# AeroQuad_v213.net
KiCad netlist of a schematic drawn in EAGLE
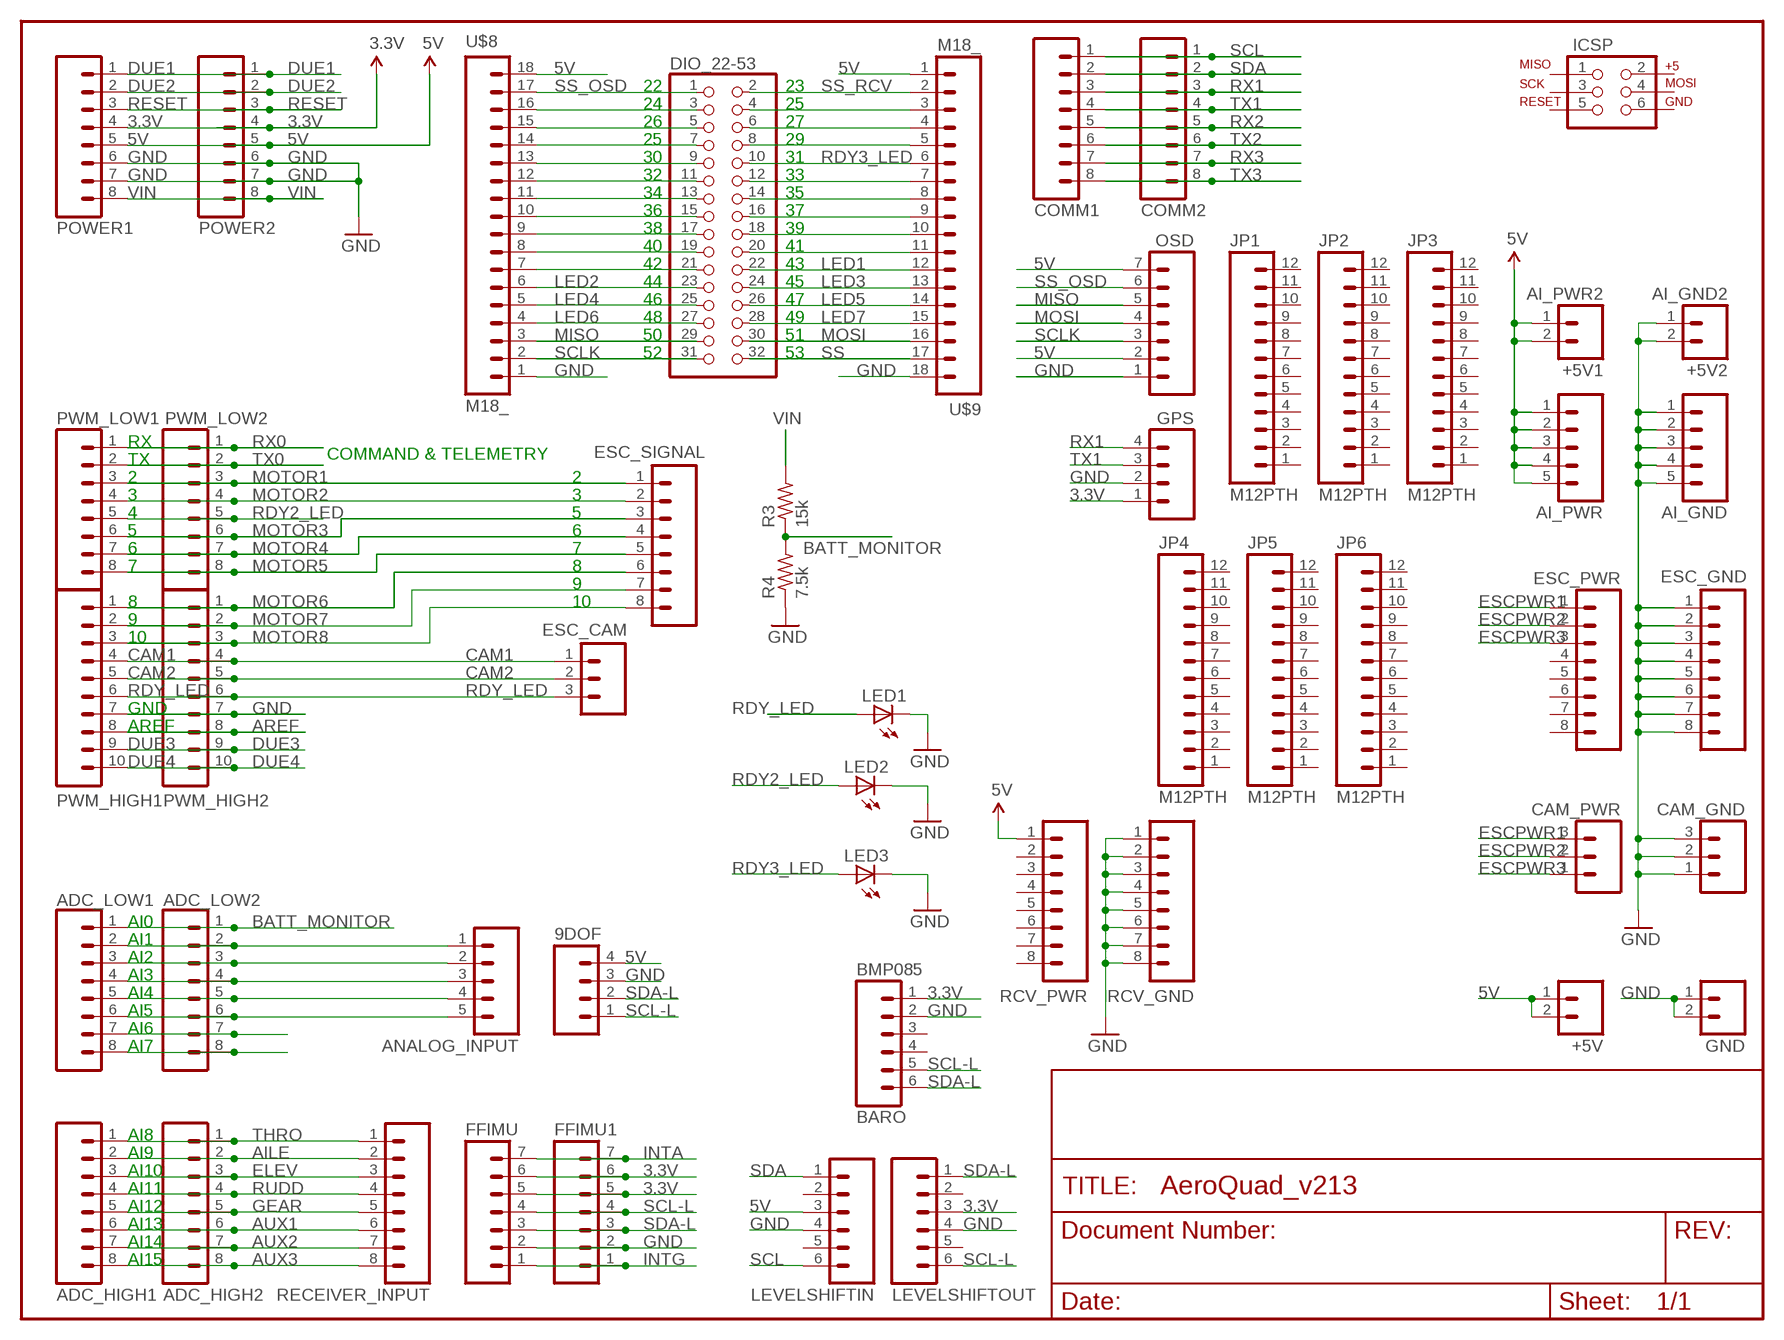
[diagram p0: schematic, sheet 1]

(export (version "E")
  (design (tool "Eeschema 10.0.6"))
  (components
    (comp (ref "+5V")
      (value "M02PTH")
      (footprint "eagle-import:1X02")
      (libsource (lib "eagle-import") (part "M02PTH"))
    )
    (comp (ref "+5V1")
      (value "AI_PWR2")
      (footprint "eagle-import:1X02")
      (libsource (lib "eagle-import") (part "M02PTH"))
    )
    (comp (ref "+5V2")
      (value "AI_GND2")
      (footprint "eagle-import:1X02")
      (libsource (lib "eagle-import") (part "M02PTH"))
    )
    (comp (ref "9DOF")
      (value "M04LOCK")
      (footprint "eagle-import:1X04_LOCK")
      (libsource (lib "eagle-import") (part "M04LOCK"))
    )
    (comp (ref "ADC_HIGH1")
      (value "M08LOCK")
      (footprint "eagle-import:1X08_LOCK")
      (libsource (lib "eagle-import") (part "M08LOCK"))
    )
    (comp (ref "ADC_HIGH2")
      (value "M08LOCK")
      (footprint "eagle-import:1X08_LOCK")
      (libsource (lib "eagle-import") (part "M08LOCK"))
    )
    (comp (ref "ADC_LOW1")
      (value "M08LOCK")
      (footprint "eagle-import:1X08_LOCK")
      (libsource (lib "eagle-import") (part "M08LOCK"))
    )
    (comp (ref "ADC_LOW2")
      (value "M08LOCK")
      (footprint "eagle-import:1X08_LOCK")
      (libsource (lib "eagle-import") (part "M08LOCK"))
    )
    (comp (ref "AI_GND")
      (value "M05LOCK")
      (footprint "eagle-import:1X05_LOCK")
      (libsource (lib "eagle-import") (part "M05LOCK"))
    )
    (comp (ref "AI_PWR")
      (value "M05LOCK")
      (footprint "eagle-import:1X05_LOCK")
      (libsource (lib "eagle-import") (part "M05LOCK"))
    )
    (comp (ref "ANALOG_INPUT")
      (value "M05LOCK")
      (footprint "eagle-import:1X05_LOCK")
      (libsource (lib "eagle-import") (part "M05LOCK"))
    )
    (comp (ref "BARO")
      (value "BMP085")
      (footprint "eagle-import:1X06_LOCK")
      (libsource (lib "eagle-import") (part "M06LOCK"))
    )
    (comp (ref "CAM_GND")
      (value "M03LOCK")
      (footprint "eagle-import:1X03_LOCK")
      (libsource (lib "eagle-import") (part "M03LOCK"))
    )
    (comp (ref "CAM_PWR")
      (value "M03LOCK")
      (footprint "eagle-import:1X03_LOCK")
      (libsource (lib "eagle-import") (part "M03LOCK"))
    )
    (comp (ref "COMM1")
      (value "M08LOCK")
      (footprint "eagle-import:1X08_LOCK")
      (libsource (lib "eagle-import") (part "M08LOCK"))
    )
    (comp (ref "COMM2")
      (value "M08LOCK")
      (footprint "eagle-import:1X08_LOCK")
      (libsource (lib "eagle-import") (part "M08LOCK"))
    )
    (comp (ref "DIO_22-53")
      (value "PINHD-2X16")
      (footprint "eagle-import:2X16")
      (libsource (lib "eagle-import") (part "PINHD-2X16"))
    )
    (comp (ref "ESC_CAM")
      (value "M03LOCK")
      (footprint "eagle-import:1X03_LOCK")
      (libsource (lib "eagle-import") (part "M03LOCK"))
    )
    (comp (ref "ESC_GND")
      (value "M10LOCK")
      (footprint "eagle-import:1X08_LOCK")
      (libsource (lib "eagle-import") (part "M08LOCK"))
    )
    (comp (ref "ESC_PWR")
      (value "M10LOCK")
      (footprint "eagle-import:1X08_LOCK")
      (libsource (lib "eagle-import") (part "M08LOCK"))
    )
    (comp (ref "ESC_SIGNAL")
      (value "M10LOCK")
      (footprint "eagle-import:1X08_LOCK")
      (libsource (lib "eagle-import") (part "M08LOCK"))
    )
    (comp (ref "FFIMU")
      (value "M07LOCK")
      (footprint "eagle-import:1X07_LOCK")
      (libsource (lib "eagle-import") (part "M07LOCK"))
    )
    (comp (ref "FFIMU1")
      (value "M07LOCK")
      (footprint "eagle-import:1X07_LOCK")
      (libsource (lib "eagle-import") (part "M07LOCK"))
    )
    (comp (ref "GND")
      (value "M02PTH")
      (footprint "eagle-import:1X02")
      (libsource (lib "eagle-import") (part "M02PTH"))
    )
    (comp (ref "GPS")
      (value "M04LOCK")
      (footprint "eagle-import:1X04_LOCK")
      (libsource (lib "eagle-import") (part "M04LOCK"))
    )
    (comp (ref "ICSP")
      (value "AVR_SPI_PRG_6NS")
      (footprint "eagle-import:2X3-NS")
      (libsource (lib "eagle-import") (part "AVR_SPI_PRG_6NS"))
    )
    (comp (ref "JP1")
      (value "M12PTH")
      (footprint "eagle-import:1X12")
      (libsource (lib "eagle-import") (part "M12PTH"))
    )
    (comp (ref "JP2")
      (value "M12PTH")
      (footprint "eagle-import:1X12")
      (libsource (lib "eagle-import") (part "M12PTH"))
    )
    (comp (ref "JP3")
      (value "M12PTH")
      (footprint "eagle-import:1X12")
      (libsource (lib "eagle-import") (part "M12PTH"))
    )
    (comp (ref "JP4")
      (value "M12PTH")
      (footprint "eagle-import:1X12")
      (libsource (lib "eagle-import") (part "M12PTH"))
    )
    (comp (ref "JP5")
      (value "M12PTH")
      (footprint "eagle-import:1X12")
      (libsource (lib "eagle-import") (part "M12PTH"))
    )
    (comp (ref "JP6")
      (value "M12PTH")
      (footprint "eagle-import:1X12")
      (libsource (lib "eagle-import") (part "M12PTH"))
    )
    (comp (ref "LED1")
      (value "LED5MM")
      (footprint "eagle-import:LED5MM")
      (libsource (lib "eagle-import") (part "LED5MM"))
    )
    (comp (ref "LED2")
      (value "LED5MM")
      (footprint "eagle-import:LED5MM")
      (libsource (lib "eagle-import") (part "LED5MM"))
    )
    (comp (ref "LED3")
      (value "LED5MM")
      (footprint "eagle-import:LED5MM")
      (libsource (lib "eagle-import") (part "LED5MM"))
    )
    (comp (ref "LEVELSHIFTIN")
      (value "M06LOCK")
      (footprint "eagle-import:1X06_LOCK")
      (libsource (lib "eagle-import") (part "M06LOCK"))
    )
    (comp (ref "LEVELSHIFTOUT")
      (value "M06LOCK")
      (footprint "eagle-import:1X06_LOCK")
      (libsource (lib "eagle-import") (part "M06LOCK"))
    )
    (comp (ref "OSD")
      (value "M07LOCK")
      (footprint "eagle-import:1X07_LOCK")
      (libsource (lib "eagle-import") (part "M07LOCK"))
    )
    (comp (ref "POWER1")
      (value "M08LOCK")
      (footprint "eagle-import:1X08_LOCK")
      (libsource (lib "eagle-import") (part "M08LOCK"))
    )
    (comp (ref "POWER2")
      (value "M08LOCK")
      (footprint "eagle-import:1X08_LOCK")
      (libsource (lib "eagle-import") (part "M08LOCK"))
    )
    (comp (ref "PWM_HIGH1")
      (value "M10LOCK")
      (footprint "eagle-import:1X10_LOCK")
      (libsource (lib "eagle-import") (part "M10LOCK"))
    )
    (comp (ref "PWM_HIGH2")
      (value "M10LOCK")
      (footprint "eagle-import:1X10_LOCK")
      (libsource (lib "eagle-import") (part "M10LOCK"))
    )
    (comp (ref "PWM_LOW1")
      (value "M08LOCK")
      (footprint "eagle-import:1X08_LOCK")
      (libsource (lib "eagle-import") (part "M08LOCK"))
    )
    (comp (ref "PWM_LOW2")
      (value "M08LOCK")
      (footprint "eagle-import:1X08_LOCK")
      (libsource (lib "eagle-import") (part "M08LOCK"))
    )
    (comp (ref "R3")
      (value "15k")
      (footprint "eagle-import:0204_5")
      (libsource (lib "eagle-import") (part "R-US_0204/5"))
    )
    (comp (ref "R4")
      (value "7.5k")
      (footprint "eagle-import:0204_5")
      (libsource (lib "eagle-import") (part "R-US_0204/5"))
    )
    (comp (ref "RCV_GND")
      (value "M10LOCK")
      (footprint "eagle-import:1X08_LOCK")
      (libsource (lib "eagle-import") (part "M08LOCK"))
    )
    (comp (ref "RCV_PWR")
      (value "M10LOCK")
      (footprint "eagle-import:1X08_LOCK")
      (libsource (lib "eagle-import") (part "M08LOCK"))
    )
    (comp (ref "RECEIVER_INPUT")
      (value "M08LOCK")
      (footprint "eagle-import:1X08_LOCK")
      (libsource (lib "eagle-import") (part "M08LOCK"))
    )
    (comp (ref "U$8")
      (value "M18_")
      (footprint "eagle-import:1X18")
      (libsource (lib "eagle-import") (part "M18_"))
    )
    (comp (ref "U$9")
      (value "M18_")
      (footprint "eagle-import:1X18")
      (libsource (lib "eagle-import") (part "M18_"))
    )
  )
  (nets
    (net (code "1") (name "/AILE") (class "Default")
      (node (ref "ADC_HIGH1") (pin "2") (pinfunction "2_2") (pintype "passive"))
      (node (ref "ADC_HIGH2") (pin "2") (pinfunction "2_2") (pintype "passive"))
      (node (ref "RECEIVER_INPUT") (pin "2") (pinfunction "2_2") (pintype "passive"))
    )
    (net (code "2") (name "/AREF") (class "Default")
      (node (ref "PWM_HIGH1") (pin "8") (pinfunction "8_8") (pintype "passive"))
      (node (ref "PWM_HIGH2") (pin "8") (pinfunction "8_8") (pintype "passive"))
    )
    (net (code "3") (name "/AUX1") (class "Default")
      (node (ref "ADC_HIGH1") (pin "6") (pinfunction "6_6") (pintype "passive"))
      (node (ref "ADC_HIGH2") (pin "6") (pinfunction "6_6") (pintype "passive"))
      (node (ref "RECEIVER_INPUT") (pin "6") (pinfunction "6_6") (pintype "passive"))
    )
    (net (code "4") (name "/AUX2") (class "Default")
      (node (ref "ADC_HIGH1") (pin "7") (pinfunction "7_7") (pintype "passive"))
      (node (ref "ADC_HIGH2") (pin "7") (pinfunction "7_7") (pintype "passive"))
      (node (ref "RECEIVER_INPUT") (pin "7") (pinfunction "7_7") (pintype "passive"))
    )
    (net (code "5") (name "/AUX3") (class "Default")
      (node (ref "ADC_HIGH1") (pin "8") (pinfunction "8_8") (pintype "passive"))
      (node (ref "ADC_HIGH2") (pin "8") (pinfunction "8_8") (pintype "passive"))
      (node (ref "RECEIVER_INPUT") (pin "8") (pinfunction "8_8") (pintype "passive"))
    )
    (net (code "6") (name "/BATT_MONITOR") (class "Default")
      (node (ref "ADC_LOW1") (pin "1") (pinfunction "1_1") (pintype "passive"))
      (node (ref "ADC_LOW2") (pin "1") (pinfunction "1_1") (pintype "passive"))
      (node (ref "R3") (pin "1") (pinfunction "1_1") (pintype "passive"))
      (node (ref "R4") (pin "2") (pinfunction "2_2") (pintype "passive"))
    )
    (net (code "7") (name "/CAM1") (class "Default")
      (node (ref "ESC_CAM") (pin "1") (pinfunction "1_1") (pintype "passive"))
      (node (ref "PWM_HIGH1") (pin "4") (pinfunction "4_4") (pintype "passive"))
      (node (ref "PWM_HIGH2") (pin "4") (pinfunction "4_4") (pintype "passive"))
    )
    (net (code "8") (name "/CAM2") (class "Default")
      (node (ref "ESC_CAM") (pin "2") (pinfunction "2_2") (pintype "passive"))
      (node (ref "PWM_HIGH1") (pin "5") (pinfunction "5_5") (pintype "passive"))
      (node (ref "PWM_HIGH2") (pin "5") (pinfunction "5_5") (pintype "passive"))
    )
    (net (code "9") (name "/DUE1") (class "Default")
      (node (ref "POWER1") (pin "1") (pinfunction "1_1") (pintype "passive"))
      (node (ref "POWER2") (pin "1") (pinfunction "1_1") (pintype "passive"))
    )
    (net (code "10") (name "/DUE2") (class "Default")
      (node (ref "POWER1") (pin "2") (pinfunction "2_2") (pintype "passive"))
      (node (ref "POWER2") (pin "2") (pinfunction "2_2") (pintype "passive"))
    )
    (net (code "11") (name "/DUE3") (class "Default")
      (node (ref "PWM_HIGH1") (pin "9") (pinfunction "9_9") (pintype "passive"))
      (node (ref "PWM_HIGH2") (pin "9") (pinfunction "9_9") (pintype "passive"))
    )
    (net (code "12") (name "/DUE4") (class "Default")
      (node (ref "PWM_HIGH1") (pin "10") (pinfunction "10_10") (pintype "passive"))
      (node (ref "PWM_HIGH2") (pin "10") (pinfunction "10_10") (pintype "passive"))
    )
    (net (code "13") (name "/ELEV") (class "Default")
      (node (ref "ADC_HIGH1") (pin "3") (pinfunction "3_3") (pintype "passive"))
      (node (ref "ADC_HIGH2") (pin "3") (pinfunction "3_3") (pintype "passive"))
      (node (ref "RECEIVER_INPUT") (pin "3") (pinfunction "3_3") (pintype "passive"))
    )
    (net (code "14") (name "/ESCPWR1") (class "Default")
      (node (ref "CAM_PWR") (pin "3") (pinfunction "3_3") (pintype "passive"))
      (node (ref "ESC_PWR") (pin "1") (pinfunction "1_1") (pintype "passive"))
    )
    (net (code "15") (name "/ESCPWR2") (class "Default")
      (node (ref "CAM_PWR") (pin "2") (pinfunction "2_2") (pintype "passive"))
      (node (ref "ESC_PWR") (pin "2") (pinfunction "2_2") (pintype "passive"))
    )
    (net (code "16") (name "/ESCPWR3") (class "Default")
      (node (ref "CAM_PWR") (pin "1") (pinfunction "1_1") (pintype "passive"))
      (node (ref "ESC_PWR") (pin "3") (pinfunction "3_3") (pintype "passive"))
    )
    (net (code "17") (name "/GEAR") (class "Default")
      (node (ref "ADC_HIGH1") (pin "5") (pinfunction "5_5") (pintype "passive"))
      (node (ref "ADC_HIGH2") (pin "5") (pinfunction "5_5") (pintype "passive"))
      (node (ref "RECEIVER_INPUT") (pin "5") (pinfunction "5_5") (pintype "passive"))
    )
    (net (code "18") (name "/INTA") (class "Default")
      (node (ref "FFIMU") (pin "7") (pinfunction "7_7") (pintype "passive"))
      (node (ref "FFIMU1") (pin "7") (pinfunction "7_7") (pintype "passive"))
    )
    (net (code "19") (name "/INTG") (class "Default")
      (node (ref "FFIMU") (pin "1") (pinfunction "1_1") (pintype "passive"))
      (node (ref "FFIMU1") (pin "1") (pinfunction "1_1") (pintype "passive"))
    )
    (net (code "20") (name "/LED1") (class "Default")
      (node (ref "DIO_22-53") (pin "22") (pinfunction "22_22") (pintype "passive"))
      (node (ref "U$9") (pin "12") (pinfunction "12_12") (pintype "passive"))
    )
    (net (code "21") (name "/LED2") (class "Default")
      (node (ref "DIO_22-53") (pin "23") (pinfunction "23_23") (pintype "passive"))
      (node (ref "U$8") (pin "6") (pinfunction "6_6") (pintype "passive"))
    )
    (net (code "22") (name "/LED3") (class "Default")
      (node (ref "DIO_22-53") (pin "24") (pinfunction "24_24") (pintype "passive"))
      (node (ref "U$9") (pin "13") (pinfunction "13_13") (pintype "passive"))
    )
    (net (code "23") (name "/LED4") (class "Default")
      (node (ref "DIO_22-53") (pin "25") (pinfunction "25_25") (pintype "passive"))
      (node (ref "U$8") (pin "5") (pinfunction "5_5") (pintype "passive"))
    )
    (net (code "24") (name "/LED5") (class "Default")
      (node (ref "DIO_22-53") (pin "26") (pinfunction "26_26") (pintype "passive"))
      (node (ref "U$9") (pin "14") (pinfunction "14_14") (pintype "passive"))
    )
    (net (code "25") (name "/LED6") (class "Default")
      (node (ref "DIO_22-53") (pin "27") (pinfunction "27_27") (pintype "passive"))
      (node (ref "U$8") (pin "4") (pinfunction "4_4") (pintype "passive"))
    )
    (net (code "26") (name "/LED7") (class "Default")
      (node (ref "DIO_22-53") (pin "28") (pinfunction "28_28") (pintype "passive"))
      (node (ref "U$9") (pin "15") (pinfunction "15_15") (pintype "passive"))
    )
    (net (code "27") (name "/MISO") (class "Default")
      (node (ref "DIO_22-53") (pin "29") (pinfunction "29_29") (pintype "passive"))
      (node (ref "OSD") (pin "5") (pinfunction "5_5") (pintype "passive"))
      (node (ref "U$8") (pin "3") (pinfunction "3_3") (pintype "passive"))
    )
    (net (code "28") (name "/MOSI") (class "Default")
      (node (ref "DIO_22-53") (pin "30") (pinfunction "30_30") (pintype "passive"))
      (node (ref "OSD") (pin "4") (pinfunction "4_4") (pintype "passive"))
      (node (ref "U$9") (pin "16") (pinfunction "16_16") (pintype "passive"))
    )
    (net (code "29") (name "/MOTOR1") (class "Default")
      (node (ref "ESC_SIGNAL") (pin "1") (pinfunction "1_1") (pintype "passive"))
      (node (ref "PWM_LOW1") (pin "3") (pinfunction "3_3") (pintype "passive"))
      (node (ref "PWM_LOW2") (pin "3") (pinfunction "3_3") (pintype "passive"))
    )
    (net (code "30") (name "/MOTOR2") (class "Default")
      (node (ref "ESC_SIGNAL") (pin "2") (pinfunction "2_2") (pintype "passive"))
      (node (ref "PWM_LOW1") (pin "4") (pinfunction "4_4") (pintype "passive"))
      (node (ref "PWM_LOW2") (pin "4") (pinfunction "4_4") (pintype "passive"))
    )
    (net (code "31") (name "/MOTOR3") (class "Default")
      (node (ref "ESC_SIGNAL") (pin "3") (pinfunction "3_3") (pintype "passive"))
      (node (ref "PWM_LOW1") (pin "6") (pinfunction "6_6") (pintype "passive"))
      (node (ref "PWM_LOW2") (pin "6") (pinfunction "6_6") (pintype "passive"))
    )
    (net (code "32") (name "/MOTOR4") (class "Default")
      (node (ref "ESC_SIGNAL") (pin "4") (pinfunction "4_4") (pintype "passive"))
      (node (ref "PWM_LOW1") (pin "7") (pinfunction "7_7") (pintype "passive"))
      (node (ref "PWM_LOW2") (pin "7") (pinfunction "7_7") (pintype "passive"))
    )
    (net (code "33") (name "/MOTOR5") (class "Default")
      (node (ref "ESC_SIGNAL") (pin "5") (pinfunction "5_5") (pintype "passive"))
      (node (ref "PWM_LOW1") (pin "8") (pinfunction "8_8") (pintype "passive"))
      (node (ref "PWM_LOW2") (pin "8") (pinfunction "8_8") (pintype "passive"))
    )
    (net (code "34") (name "/MOTOR6") (class "Default")
      (node (ref "ESC_SIGNAL") (pin "6") (pinfunction "6_6") (pintype "passive"))
      (node (ref "PWM_HIGH1") (pin "1") (pinfunction "1_1") (pintype "passive"))
      (node (ref "PWM_HIGH2") (pin "1") (pinfunction "1_1") (pintype "passive"))
    )
    (net (code "35") (name "/MOTOR7") (class "Default")
      (node (ref "ESC_SIGNAL") (pin "7") (pinfunction "7_7") (pintype "passive"))
      (node (ref "PWM_HIGH1") (pin "2") (pinfunction "2_2") (pintype "passive"))
      (node (ref "PWM_HIGH2") (pin "2") (pinfunction "2_2") (pintype "passive"))
    )
    (net (code "36") (name "/MOTOR8") (class "Default")
      (node (ref "ESC_SIGNAL") (pin "8") (pinfunction "8_8") (pintype "passive"))
      (node (ref "PWM_HIGH1") (pin "3") (pinfunction "3_3") (pintype "passive"))
      (node (ref "PWM_HIGH2") (pin "3") (pinfunction "3_3") (pintype "passive"))
    )
    (net (code "37") (name "/RDY2_LED") (class "Default")
      (node (ref "LED2") (pin "A") (pinfunction "A_A") (pintype "passive"))
      (node (ref "PWM_LOW1") (pin "5") (pinfunction "5_5") (pintype "passive"))
      (node (ref "PWM_LOW2") (pin "5") (pinfunction "5_5") (pintype "passive"))
    )
    (net (code "38") (name "/RDY3_LED") (class "Default")
      (node (ref "DIO_22-53") (pin "10") (pinfunction "10_10") (pintype "passive"))
      (node (ref "LED3") (pin "A") (pinfunction "A_A") (pintype "passive"))
      (node (ref "U$9") (pin "6") (pinfunction "6_6") (pintype "passive"))
    )
    (net (code "39") (name "/RDY_LED") (class "Default")
      (node (ref "ESC_CAM") (pin "3") (pinfunction "3_3") (pintype "passive"))
      (node (ref "LED1") (pin "A") (pinfunction "A_A") (pintype "passive"))
      (node (ref "PWM_HIGH1") (pin "6") (pinfunction "6_6") (pintype "passive"))
      (node (ref "PWM_HIGH2") (pin "6") (pinfunction "6_6") (pintype "passive"))
    )
    (net (code "40") (name "/RESET") (class "Default")
      (node (ref "POWER1") (pin "3") (pinfunction "3_3") (pintype "passive"))
      (node (ref "POWER2") (pin "3") (pinfunction "3_3") (pintype "passive"))
    )
    (net (code "41") (name "/RUDD") (class "Default")
      (node (ref "ADC_HIGH1") (pin "4") (pinfunction "4_4") (pintype "passive"))
      (node (ref "ADC_HIGH2") (pin "4") (pinfunction "4_4") (pintype "passive"))
      (node (ref "RECEIVER_INPUT") (pin "4") (pinfunction "4_4") (pintype "passive"))
    )
    (net (code "42") (name "/RX0") (class "Default")
      (node (ref "PWM_LOW1") (pin "1") (pinfunction "1_1") (pintype "passive"))
      (node (ref "PWM_LOW2") (pin "1") (pinfunction "1_1") (pintype "passive"))
    )
    (net (code "43") (name "/RX1") (class "Default")
      (node (ref "COMM1") (pin "3") (pinfunction "3_3") (pintype "passive"))
      (node (ref "COMM2") (pin "3") (pinfunction "3_3") (pintype "passive"))
      (node (ref "GPS") (pin "4") (pinfunction "4_4") (pintype "passive"))
    )
    (net (code "44") (name "/RX2") (class "Default")
      (node (ref "COMM1") (pin "5") (pinfunction "5_5") (pintype "passive"))
      (node (ref "COMM2") (pin "5") (pinfunction "5_5") (pintype "passive"))
    )
    (net (code "45") (name "/RX3") (class "Default")
      (node (ref "COMM1") (pin "7") (pinfunction "7_7") (pintype "passive"))
      (node (ref "COMM2") (pin "7") (pinfunction "7_7") (pintype "passive"))
    )
    (net (code "46") (name "/SCL") (class "Default")
      (node (ref "COMM1") (pin "1") (pinfunction "1_1") (pintype "passive"))
      (node (ref "COMM2") (pin "1") (pinfunction "1_1") (pintype "passive"))
      (node (ref "LEVELSHIFTIN") (pin "6") (pinfunction "6_6") (pintype "passive"))
    )
    (net (code "47") (name "/SCL-L") (class "Default")
      (node (ref "9DOF") (pin "1") (pinfunction "1_1") (pintype "passive"))
      (node (ref "BARO") (pin "5") (pinfunction "5_5") (pintype "passive"))
      (node (ref "FFIMU") (pin "4") (pinfunction "4_4") (pintype "passive"))
      (node (ref "FFIMU1") (pin "4") (pinfunction "4_4") (pintype "passive"))
      (node (ref "LEVELSHIFTOUT") (pin "6") (pinfunction "6_6") (pintype "passive"))
    )
    (net (code "48") (name "/SCLK") (class "Default")
      (node (ref "DIO_22-53") (pin "31") (pinfunction "31_31") (pintype "passive"))
      (node (ref "OSD") (pin "3") (pinfunction "3_3") (pintype "passive"))
      (node (ref "U$8") (pin "2") (pinfunction "2_2") (pintype "passive"))
    )
    (net (code "49") (name "/SDA") (class "Default")
      (node (ref "COMM1") (pin "2") (pinfunction "2_2") (pintype "passive"))
      (node (ref "COMM2") (pin "2") (pinfunction "2_2") (pintype "passive"))
      (node (ref "LEVELSHIFTIN") (pin "1") (pinfunction "1_1") (pintype "passive"))
    )
    (net (code "50") (name "/SDA-L") (class "Default")
      (node (ref "9DOF") (pin "2") (pinfunction "2_2") (pintype "passive"))
      (node (ref "BARO") (pin "6") (pinfunction "6_6") (pintype "passive"))
      (node (ref "FFIMU") (pin "3") (pinfunction "3_3") (pintype "passive"))
      (node (ref "FFIMU1") (pin "3") (pinfunction "3_3") (pintype "passive"))
      (node (ref "LEVELSHIFTOUT") (pin "1") (pinfunction "1_1") (pintype "passive"))
    )
    (net (code "51") (name "/SS") (class "Default")
      (node (ref "DIO_22-53") (pin "32") (pinfunction "32_32") (pintype "passive"))
      (node (ref "U$9") (pin "17") (pinfunction "17_17") (pintype "passive"))
    )
    (net (code "52") (name "/SS_OSD") (class "Default")
      (node (ref "DIO_22-53") (pin "1") (pinfunction "1_1") (pintype "passive"))
      (node (ref "OSD") (pin "6") (pinfunction "6_6") (pintype "passive"))
      (node (ref "U$8") (pin "17") (pinfunction "17_17") (pintype "passive"))
    )
    (net (code "53") (name "/SS_RCV") (class "Default")
      (node (ref "DIO_22-53") (pin "2") (pinfunction "2_2") (pintype "passive"))
      (node (ref "U$9") (pin "2") (pinfunction "2_2") (pintype "passive"))
    )
    (net (code "54") (name "/THRO") (class "Default")
      (node (ref "ADC_HIGH1") (pin "1") (pinfunction "1_1") (pintype "passive"))
      (node (ref "ADC_HIGH2") (pin "1") (pinfunction "1_1") (pintype "passive"))
      (node (ref "RECEIVER_INPUT") (pin "1") (pinfunction "1_1") (pintype "passive"))
    )
    (net (code "55") (name "/TX0") (class "Default")
      (node (ref "PWM_LOW1") (pin "2") (pinfunction "2_2") (pintype "passive"))
      (node (ref "PWM_LOW2") (pin "2") (pinfunction "2_2") (pintype "passive"))
    )
    (net (code "56") (name "/TX1") (class "Default")
      (node (ref "COMM1") (pin "4") (pinfunction "4_4") (pintype "passive"))
      (node (ref "COMM2") (pin "4") (pinfunction "4_4") (pintype "passive"))
      (node (ref "GPS") (pin "3") (pinfunction "3_3") (pintype "passive"))
    )
    (net (code "57") (name "/TX2") (class "Default")
      (node (ref "COMM1") (pin "6") (pinfunction "6_6") (pintype "passive"))
      (node (ref "COMM2") (pin "6") (pinfunction "6_6") (pintype "passive"))
    )
    (net (code "58") (name "/TX3") (class "Default")
      (node (ref "COMM1") (pin "8") (pinfunction "8_8") (pintype "passive"))
      (node (ref "COMM2") (pin "8") (pinfunction "8_8") (pintype "passive"))
    )
    (net (code "59") (name "/VIN") (class "Default")
      (node (ref "POWER1") (pin "8") (pinfunction "8_8") (pintype "passive"))
      (node (ref "POWER2") (pin "8") (pinfunction "8_8") (pintype "passive"))
      (node (ref "R3") (pin "2") (pinfunction "2_2") (pintype "passive"))
    )
    (net (code "60") (name "3.3V") (class "Default")
      (node (ref "BARO") (pin "1") (pinfunction "1_1") (pintype "passive"))
      (node (ref "FFIMU") (pin "5") (pinfunction "5_5") (pintype "passive"))
      (node (ref "FFIMU") (pin "6") (pinfunction "6_6") (pintype "passive"))
      (node (ref "FFIMU1") (pin "5") (pinfunction "5_5") (pintype "passive"))
      (node (ref "FFIMU1") (pin "6") (pinfunction "6_6") (pintype "passive"))
      (node (ref "GPS") (pin "1") (pinfunction "1_1") (pintype "passive"))
      (node (ref "LEVELSHIFTOUT") (pin "3") (pinfunction "3_3") (pintype "passive"))
      (node (ref "POWER1") (pin "4") (pinfunction "4_4") (pintype "passive"))
      (node (ref "POWER2") (pin "4") (pinfunction "4_4") (pintype "passive"))
    )
    (net (code "61") (name "5V") (class "Default")
      (node (ref "+5V") (pin "1") (pinfunction "1_1") (pintype "passive"))
      (node (ref "+5V") (pin "2") (pinfunction "2_2") (pintype "passive"))
      (node (ref "+5V1") (pin "1") (pinfunction "1_1") (pintype "passive"))
      (node (ref "+5V1") (pin "2") (pinfunction "2_2") (pintype "passive"))
      (node (ref "9DOF") (pin "4") (pinfunction "4_4") (pintype "passive"))
      (node (ref "AI_PWR") (pin "1") (pinfunction "1_1") (pintype "passive"))
      (node (ref "AI_PWR") (pin "2") (pinfunction "2_2") (pintype "passive"))
      (node (ref "AI_PWR") (pin "3") (pinfunction "3_3") (pintype "passive"))
      (node (ref "AI_PWR") (pin "4") (pinfunction "4_4") (pintype "passive"))
      (node (ref "AI_PWR") (pin "5") (pinfunction "5_5") (pintype "passive"))
      (node (ref "LEVELSHIFTIN") (pin "3") (pinfunction "3_3") (pintype "passive"))
      (node (ref "OSD") (pin "2") (pinfunction "2_2") (pintype "passive"))
      (node (ref "OSD") (pin "7") (pinfunction "7_7") (pintype "passive"))
      (node (ref "POWER1") (pin "5") (pinfunction "5_5") (pintype "passive"))
      (node (ref "POWER2") (pin "5") (pinfunction "5_5") (pintype "passive"))
      (node (ref "RCV_PWR") (pin "1") (pinfunction "1_1") (pintype "passive"))
      (node (ref "U$8") (pin "18") (pinfunction "18_18") (pintype "passive"))
      (node (ref "U$9") (pin "1") (pinfunction "1_1") (pintype "passive"))
    )
    (net (code "62") (name "GND") (class "Default")
      (node (ref "+5V2") (pin "1") (pinfunction "1_1") (pintype "passive"))
      (node (ref "+5V2") (pin "2") (pinfunction "2_2") (pintype "passive"))
      (node (ref "9DOF") (pin "3") (pinfunction "3_3") (pintype "passive"))
      (node (ref "AI_GND") (pin "1") (pinfunction "1_1") (pintype "passive"))
      (node (ref "AI_GND") (pin "2") (pinfunction "2_2") (pintype "passive"))
      (node (ref "AI_GND") (pin "3") (pinfunction "3_3") (pintype "passive"))
      (node (ref "AI_GND") (pin "4") (pinfunction "4_4") (pintype "passive"))
      (node (ref "AI_GND") (pin "5") (pinfunction "5_5") (pintype "passive"))
      (node (ref "BARO") (pin "2") (pinfunction "2_2") (pintype "passive"))
      (node (ref "CAM_GND") (pin "1") (pinfunction "1_1") (pintype "passive"))
      (node (ref "CAM_GND") (pin "2") (pinfunction "2_2") (pintype "passive"))
      (node (ref "CAM_GND") (pin "3") (pinfunction "3_3") (pintype "passive"))
      (node (ref "ESC_GND") (pin "1") (pinfunction "1_1") (pintype "passive"))
      (node (ref "ESC_GND") (pin "2") (pinfunction "2_2") (pintype "passive"))
      (node (ref "ESC_GND") (pin "3") (pinfunction "3_3") (pintype "passive"))
      (node (ref "ESC_GND") (pin "4") (pinfunction "4_4") (pintype "passive"))
      (node (ref "ESC_GND") (pin "5") (pinfunction "5_5") (pintype "passive"))
      (node (ref "ESC_GND") (pin "6") (pinfunction "6_6") (pintype "passive"))
      (node (ref "ESC_GND") (pin "7") (pinfunction "7_7") (pintype "passive"))
      (node (ref "ESC_GND") (pin "8") (pinfunction "8_8") (pintype "passive"))
      (node (ref "FFIMU") (pin "2") (pinfunction "2_2") (pintype "passive"))
      (node (ref "FFIMU1") (pin "2") (pinfunction "2_2") (pintype "passive"))
      (node (ref "GND") (pin "1") (pinfunction "1_1") (pintype "passive"))
      (node (ref "GND") (pin "2") (pinfunction "2_2") (pintype "passive"))
      (node (ref "GPS") (pin "2") (pinfunction "2_2") (pintype "passive"))
      (node (ref "LED1") (pin "K") (pinfunction "C_K") (pintype "passive"))
      (node (ref "LED2") (pin "K") (pinfunction "C_K") (pintype "passive"))
      (node (ref "LED3") (pin "K") (pinfunction "C_K") (pintype "passive"))
      (node (ref "LEVELSHIFTIN") (pin "4") (pinfunction "4_4") (pintype "passive"))
      (node (ref "LEVELSHIFTOUT") (pin "4") (pinfunction "4_4") (pintype "passive"))
      (node (ref "OSD") (pin "1") (pinfunction "1_1") (pintype "passive"))
      (node (ref "POWER1") (pin "6") (pinfunction "6_6") (pintype "passive"))
      (node (ref "POWER1") (pin "7") (pinfunction "7_7") (pintype "passive"))
      (node (ref "POWER2") (pin "6") (pinfunction "6_6") (pintype "passive"))
      (node (ref "POWER2") (pin "7") (pinfunction "7_7") (pintype "passive"))
      (node (ref "PWM_HIGH1") (pin "7") (pinfunction "7_7") (pintype "passive"))
      (node (ref "PWM_HIGH2") (pin "7") (pinfunction "7_7") (pintype "passive"))
      (node (ref "R4") (pin "1") (pinfunction "1_1") (pintype "passive"))
      (node (ref "RCV_GND") (pin "1") (pinfunction "1_1") (pintype "passive"))
      (node (ref "RCV_GND") (pin "2") (pinfunction "2_2") (pintype "passive"))
      (node (ref "RCV_GND") (pin "3") (pinfunction "3_3") (pintype "passive"))
      (node (ref "RCV_GND") (pin "4") (pinfunction "4_4") (pintype "passive"))
      (node (ref "RCV_GND") (pin "5") (pinfunction "5_5") (pintype "passive"))
      (node (ref "RCV_GND") (pin "6") (pinfunction "6_6") (pintype "passive"))
      (node (ref "RCV_GND") (pin "7") (pinfunction "7_7") (pintype "passive"))
      (node (ref "RCV_GND") (pin "8") (pinfunction "8_8") (pintype "passive"))
      (node (ref "U$8") (pin "1") (pinfunction "1_1") (pintype "passive"))
      (node (ref "U$9") (pin "18") (pinfunction "18_18") (pintype "passive"))
    )
    (net (code "63") (name "Net-(ADC_LOW1-Pad2)") (class "Default")
      (node (ref "ADC_LOW1") (pin "2") (pinfunction "2_2") (pintype "passive"))
      (node (ref "ADC_LOW2") (pin "2") (pinfunction "2_2") (pintype "passive"))
      (node (ref "ANALOG_INPUT") (pin "1") (pinfunction "1_1") (pintype "passive"))
    )
    (net (code "64") (name "Net-(ADC_LOW1-Pad3)") (class "Default")
      (node (ref "ADC_LOW1") (pin "3") (pinfunction "3_3") (pintype "passive"))
      (node (ref "ADC_LOW2") (pin "3") (pinfunction "3_3") (pintype "passive"))
      (node (ref "ANALOG_INPUT") (pin "2") (pinfunction "2_2") (pintype "passive"))
    )
    (net (code "65") (name "Net-(ADC_LOW1-Pad4)") (class "Default")
      (node (ref "ADC_LOW1") (pin "4") (pinfunction "4_4") (pintype "passive"))
      (node (ref "ADC_LOW2") (pin "4") (pinfunction "4_4") (pintype "passive"))
      (node (ref "ANALOG_INPUT") (pin "3") (pinfunction "3_3") (pintype "passive"))
    )
    (net (code "66") (name "Net-(ADC_LOW1-Pad5)") (class "Default")
      (node (ref "ADC_LOW1") (pin "5") (pinfunction "5_5") (pintype "passive"))
      (node (ref "ADC_LOW2") (pin "5") (pinfunction "5_5") (pintype "passive"))
      (node (ref "ANALOG_INPUT") (pin "4") (pinfunction "4_4") (pintype "passive"))
    )
    (net (code "67") (name "Net-(ADC_LOW1-Pad6)") (class "Default")
      (node (ref "ADC_LOW1") (pin "6") (pinfunction "6_6") (pintype "passive"))
      (node (ref "ADC_LOW2") (pin "6") (pinfunction "6_6") (pintype "passive"))
      (node (ref "ANALOG_INPUT") (pin "5") (pinfunction "5_5") (pintype "passive"))
    )
    (net (code "68") (name "Net-(ADC_LOW1-Pad7)") (class "Default")
      (node (ref "ADC_LOW1") (pin "7") (pinfunction "7_7") (pintype "passive"))
      (node (ref "ADC_LOW2") (pin "7") (pinfunction "7_7") (pintype "passive"))
    )
    (net (code "69") (name "Net-(ADC_LOW1-Pad8)") (class "Default")
      (node (ref "ADC_LOW1") (pin "8") (pinfunction "8_8") (pintype "passive"))
      (node (ref "ADC_LOW2") (pin "8") (pinfunction "8_8") (pintype "passive"))
    )
    (net (code "70") (name "Net-(DIO_22-53-Pad3)") (class "Default")
      (node (ref "DIO_22-53") (pin "3") (pinfunction "3_3") (pintype "passive"))
      (node (ref "U$8") (pin "16") (pinfunction "16_16") (pintype "passive"))
    )
    (net (code "71") (name "Net-(DIO_22-53-Pad4)") (class "Default")
      (node (ref "DIO_22-53") (pin "4") (pinfunction "4_4") (pintype "passive"))
      (node (ref "U$9") (pin "3") (pinfunction "3_3") (pintype "passive"))
    )
    (net (code "72") (name "Net-(DIO_22-53-Pad5)") (class "Default")
      (node (ref "DIO_22-53") (pin "5") (pinfunction "5_5") (pintype "passive"))
      (node (ref "U$8") (pin "15") (pinfunction "15_15") (pintype "passive"))
    )
    (net (code "73") (name "Net-(DIO_22-53-Pad6)") (class "Default")
      (node (ref "DIO_22-53") (pin "6") (pinfunction "6_6") (pintype "passive"))
      (node (ref "U$9") (pin "4") (pinfunction "4_4") (pintype "passive"))
    )
    (net (code "74") (name "Net-(DIO_22-53-Pad7)") (class "Default")
      (node (ref "DIO_22-53") (pin "7") (pinfunction "7_7") (pintype "passive"))
      (node (ref "U$8") (pin "14") (pinfunction "14_14") (pintype "passive"))
    )
    (net (code "75") (name "Net-(DIO_22-53-Pad8)") (class "Default")
      (node (ref "DIO_22-53") (pin "8") (pinfunction "8_8") (pintype "passive"))
      (node (ref "U$9") (pin "5") (pinfunction "5_5") (pintype "passive"))
    )
    (net (code "76") (name "Net-(DIO_22-53-Pad9)") (class "Default")
      (node (ref "DIO_22-53") (pin "9") (pinfunction "9_9") (pintype "passive"))
      (node (ref "U$8") (pin "13") (pinfunction "13_13") (pintype "passive"))
    )
    (net (code "77") (name "Net-(DIO_22-53-Pad11)") (class "Default")
      (node (ref "DIO_22-53") (pin "11") (pinfunction "11_11") (pintype "passive"))
      (node (ref "U$8") (pin "12") (pinfunction "12_12") (pintype "passive"))
    )
    (net (code "78") (name "Net-(DIO_22-53-Pad12)") (class "Default")
      (node (ref "DIO_22-53") (pin "12") (pinfunction "12_12") (pintype "passive"))
      (node (ref "U$9") (pin "7") (pinfunction "7_7") (pintype "passive"))
    )
    (net (code "79") (name "Net-(DIO_22-53-Pad13)") (class "Default")
      (node (ref "DIO_22-53") (pin "13") (pinfunction "13_13") (pintype "passive"))
      (node (ref "U$8") (pin "11") (pinfunction "11_11") (pintype "passive"))
    )
    (net (code "80") (name "Net-(DIO_22-53-Pad14)") (class "Default")
      (node (ref "DIO_22-53") (pin "14") (pinfunction "14_14") (pintype "passive"))
      (node (ref "U$9") (pin "8") (pinfunction "8_8") (pintype "passive"))
    )
    (net (code "81") (name "Net-(DIO_22-53-Pad15)") (class "Default")
      (node (ref "DIO_22-53") (pin "15") (pinfunction "15_15") (pintype "passive"))
      (node (ref "U$8") (pin "10") (pinfunction "10_10") (pintype "passive"))
    )
    (net (code "82") (name "Net-(DIO_22-53-Pad16)") (class "Default")
      (node (ref "DIO_22-53") (pin "16") (pinfunction "16_16") (pintype "passive"))
      (node (ref "U$9") (pin "9") (pinfunction "9_9") (pintype "passive"))
    )
    (net (code "83") (name "Net-(DIO_22-53-Pad17)") (class "Default")
      (node (ref "DIO_22-53") (pin "17") (pinfunction "17_17") (pintype "passive"))
      (node (ref "U$8") (pin "9") (pinfunction "9_9") (pintype "passive"))
    )
    (net (code "84") (name "Net-(DIO_22-53-Pad18)") (class "Default")
      (node (ref "DIO_22-53") (pin "18") (pinfunction "18_18") (pintype "passive"))
      (node (ref "U$9") (pin "10") (pinfunction "10_10") (pintype "passive"))
    )
    (net (code "85") (name "Net-(DIO_22-53-Pad19)") (class "Default")
      (node (ref "DIO_22-53") (pin "19") (pinfunction "19_19") (pintype "passive"))
      (node (ref "U$8") (pin "8") (pinfunction "8_8") (pintype "passive"))
    )
    (net (code "86") (name "Net-(DIO_22-53-Pad20)") (class "Default")
      (node (ref "DIO_22-53") (pin "20") (pinfunction "20_20") (pintype "passive"))
      (node (ref "U$9") (pin "11") (pinfunction "11_11") (pintype "passive"))
    )
    (net (code "87") (name "Net-(DIO_22-53-Pad21)") (class "Default")
      (node (ref "DIO_22-53") (pin "21") (pinfunction "21_21") (pintype "passive"))
      (node (ref "U$8") (pin "7") (pinfunction "7_7") (pintype "passive"))
    )
    (net (code "88") (name "unconnected-(BARO-Pad3)") (class "Default")
      (node (ref "BARO") (pin "3") (pinfunction "3_3") (pintype "passive"))
    )
    (net (code "89") (name "unconnected-(BARO-Pad4)") (class "Default")
      (node (ref "BARO") (pin "4") (pinfunction "4_4") (pintype "passive"))
    )
    (net (code "90") (name "unconnected-(ESC_PWR-Pad4)") (class "Default")
      (node (ref "ESC_PWR") (pin "4") (pinfunction "4_4") (pintype "passive"))
    )
    (net (code "91") (name "unconnected-(ESC_PWR-Pad5)") (class "Default")
      (node (ref "ESC_PWR") (pin "5") (pinfunction "5_5") (pintype "passive"))
    )
    (net (code "92") (name "unconnected-(ESC_PWR-Pad6)") (class "Default")
      (node (ref "ESC_PWR") (pin "6") (pinfunction "6_6") (pintype "passive"))
    )
    (net (code "93") (name "unconnected-(ESC_PWR-Pad7)") (class "Default")
      (node (ref "ESC_PWR") (pin "7") (pinfunction "7_7") (pintype "passive"))
    )
    (net (code "94") (name "unconnected-(ESC_PWR-Pad8)") (class "Default")
      (node (ref "ESC_PWR") (pin "8") (pinfunction "8_8") (pintype "passive"))
    )
    (net (code "95") (name "unconnected-(ICSP-Pad1)") (class "Default")
      (node (ref "ICSP") (pin "1") (pinfunction "1_1") (pintype "passive"))
    )
    (net (code "96") (name "unconnected-(ICSP-Pad2)") (class "Default")
      (node (ref "ICSP") (pin "2") (pinfunction "2_2") (pintype "passive"))
    )
    (net (code "97") (name "unconnected-(ICSP-Pad3)") (class "Default")
      (node (ref "ICSP") (pin "3") (pinfunction "3_3") (pintype "passive"))
    )
    (net (code "98") (name "unconnected-(ICSP-Pad4)") (class "Default")
      (node (ref "ICSP") (pin "4") (pinfunction "4_4") (pintype "passive"))
    )
    (net (code "99") (name "unconnected-(ICSP-Pad5)") (class "Default")
      (node (ref "ICSP") (pin "5") (pinfunction "5_5") (pintype "passive"))
    )
    (net (code "100") (name "unconnected-(ICSP-Pad6)") (class "Default")
      (node (ref "ICSP") (pin "6") (pinfunction "6_6") (pintype "passive"))
    )
    (net (code "101") (name "unconnected-(JP1-Pad1)") (class "Default")
      (node (ref "JP1") (pin "1") (pinfunction "1_1") (pintype "passive"))
    )
    (net (code "102") (name "unconnected-(JP1-Pad2)") (class "Default")
      (node (ref "JP1") (pin "2") (pinfunction "2_2") (pintype "passive"))
    )
    (net (code "103") (name "unconnected-(JP1-Pad3)") (class "Default")
      (node (ref "JP1") (pin "3") (pinfunction "3_3") (pintype "passive"))
    )
    (net (code "104") (name "unconnected-(JP1-Pad4)") (class "Default")
      (node (ref "JP1") (pin "4") (pinfunction "4_4") (pintype "passive"))
    )
    (net (code "105") (name "unconnected-(JP1-Pad5)") (class "Default")
      (node (ref "JP1") (pin "5") (pinfunction "5_5") (pintype "passive"))
    )
    (net (code "106") (name "unconnected-(JP1-Pad6)") (class "Default")
      (node (ref "JP1") (pin "6") (pinfunction "6_6") (pintype "passive"))
    )
    (net (code "107") (name "unconnected-(JP1-Pad7)") (class "Default")
      (node (ref "JP1") (pin "7") (pinfunction "7_7") (pintype "passive"))
    )
    (net (code "108") (name "unconnected-(JP1-Pad8)") (class "Default")
      (node (ref "JP1") (pin "8") (pinfunction "8_8") (pintype "passive"))
    )
    (net (code "109") (name "unconnected-(JP1-Pad9)") (class "Default")
      (node (ref "JP1") (pin "9") (pinfunction "9_9") (pintype "passive"))
    )
    (net (code "110") (name "unconnected-(JP1-Pad10)") (class "Default")
      (node (ref "JP1") (pin "10") (pinfunction "10_10") (pintype "passive"))
    )
    (net (code "111") (name "unconnected-(JP1-Pad11)") (class "Default")
      (node (ref "JP1") (pin "11") (pinfunction "11_11") (pintype "passive"))
    )
    (net (code "112") (name "unconnected-(JP1-Pad12)") (class "Default")
      (node (ref "JP1") (pin "12") (pinfunction "12_12") (pintype "passive"))
    )
    (net (code "113") (name "unconnected-(JP2-Pad1)") (class "Default")
      (node (ref "JP2") (pin "1") (pinfunction "1_1") (pintype "passive"))
    )
    (net (code "114") (name "unconnected-(JP2-Pad2)") (class "Default")
      (node (ref "JP2") (pin "2") (pinfunction "2_2") (pintype "passive"))
    )
    (net (code "115") (name "unconnected-(JP2-Pad3)") (class "Default")
      (node (ref "JP2") (pin "3") (pinfunction "3_3") (pintype "passive"))
    )
    (net (code "116") (name "unconnected-(JP2-Pad4)") (class "Default")
      (node (ref "JP2") (pin "4") (pinfunction "4_4") (pintype "passive"))
    )
    (net (code "117") (name "unconnected-(JP2-Pad5)") (class "Default")
      (node (ref "JP2") (pin "5") (pinfunction "5_5") (pintype "passive"))
    )
    (net (code "118") (name "unconnected-(JP2-Pad6)") (class "Default")
      (node (ref "JP2") (pin "6") (pinfunction "6_6") (pintype "passive"))
    )
    (net (code "119") (name "unconnected-(JP2-Pad7)") (class "Default")
      (node (ref "JP2") (pin "7") (pinfunction "7_7") (pintype "passive"))
    )
    (net (code "120") (name "unconnected-(JP2-Pad8)") (class "Default")
      (node (ref "JP2") (pin "8") (pinfunction "8_8") (pintype "passive"))
    )
    (net (code "121") (name "unconnected-(JP2-Pad9)") (class "Default")
      (node (ref "JP2") (pin "9") (pinfunction "9_9") (pintype "passive"))
    )
    (net (code "122") (name "unconnected-(JP2-Pad10)") (class "Default")
      (node (ref "JP2") (pin "10") (pinfunction "10_10") (pintype "passive"))
    )
    (net (code "123") (name "unconnected-(JP2-Pad11)") (class "Default")
      (node (ref "JP2") (pin "11") (pinfunction "11_11") (pintype "passive"))
    )
    (net (code "124") (name "unconnected-(JP2-Pad12)") (class "Default")
      (node (ref "JP2") (pin "12") (pinfunction "12_12") (pintype "passive"))
    )
    (net (code "125") (name "unconnected-(JP3-Pad1)") (class "Default")
      (node (ref "JP3") (pin "1") (pinfunction "1_1") (pintype "passive"))
    )
    (net (code "126") (name "unconnected-(JP3-Pad2)") (class "Default")
      (node (ref "JP3") (pin "2") (pinfunction "2_2") (pintype "passive"))
    )
    (net (code "127") (name "unconnected-(JP3-Pad3)") (class "Default")
      (node (ref "JP3") (pin "3") (pinfunction "3_3") (pintype "passive"))
    )
    (net (code "128") (name "unconnected-(JP3-Pad4)") (class "Default")
      (node (ref "JP3") (pin "4") (pinfunction "4_4") (pintype "passive"))
    )
    (net (code "129") (name "unconnected-(JP3-Pad5)") (class "Default")
      (node (ref "JP3") (pin "5") (pinfunction "5_5") (pintype "passive"))
    )
    (net (code "130") (name "unconnected-(JP3-Pad6)") (class "Default")
      (node (ref "JP3") (pin "6") (pinfunction "6_6") (pintype "passive"))
    )
    (net (code "131") (name "unconnected-(JP3-Pad7)") (class "Default")
      (node (ref "JP3") (pin "7") (pinfunction "7_7") (pintype "passive"))
    )
    (net (code "132") (name "unconnected-(JP3-Pad8)") (class "Default")
      (node (ref "JP3") (pin "8") (pinfunction "8_8") (pintype "passive"))
    )
    (net (code "133") (name "unconnected-(JP3-Pad9)") (class "Default")
      (node (ref "JP3") (pin "9") (pinfunction "9_9") (pintype "passive"))
    )
    (net (code "134") (name "unconnected-(JP3-Pad10)") (class "Default")
      (node (ref "JP3") (pin "10") (pinfunction "10_10") (pintype "passive"))
    )
    (net (code "135") (name "unconnected-(JP3-Pad11)") (class "Default")
      (node (ref "JP3") (pin "11") (pinfunction "11_11") (pintype "passive"))
    )
    (net (code "136") (name "unconnected-(JP3-Pad12)") (class "Default")
      (node (ref "JP3") (pin "12") (pinfunction "12_12") (pintype "passive"))
    )
    (net (code "137") (name "unconnected-(JP4-Pad1)") (class "Default")
      (node (ref "JP4") (pin "1") (pinfunction "1_1") (pintype "passive"))
    )
    (net (code "138") (name "unconnected-(JP4-Pad2)") (class "Default")
      (node (ref "JP4") (pin "2") (pinfunction "2_2") (pintype "passive"))
    )
    (net (code "139") (name "unconnected-(JP4-Pad3)") (class "Default")
      (node (ref "JP4") (pin "3") (pinfunction "3_3") (pintype "passive"))
    )
    (net (code "140") (name "unconnected-(JP4-Pad4)") (class "Default")
      (node (ref "JP4") (pin "4") (pinfunction "4_4") (pintype "passive"))
    )
    (net (code "141") (name "unconnected-(JP4-Pad5)") (class "Default")
      (node (ref "JP4") (pin "5") (pinfunction "5_5") (pintype "passive"))
    )
    (net (code "142") (name "unconnected-(JP4-Pad6)") (class "Default")
      (node (ref "JP4") (pin "6") (pinfunction "6_6") (pintype "passive"))
    )
    (net (code "143") (name "unconnected-(JP4-Pad7)") (class "Default")
      (node (ref "JP4") (pin "7") (pinfunction "7_7") (pintype "passive"))
    )
    (net (code "144") (name "unconnected-(JP4-Pad8)") (class "Default")
      (node (ref "JP4") (pin "8") (pinfunction "8_8") (pintype "passive"))
    )
    (net (code "145") (name "unconnected-(JP4-Pad9)") (class "Default")
      (node (ref "JP4") (pin "9") (pinfunction "9_9") (pintype "passive"))
    )
    (net (code "146") (name "unconnected-(JP4-Pad10)") (class "Default")
      (node (ref "JP4") (pin "10") (pinfunction "10_10") (pintype "passive"))
    )
    (net (code "147") (name "unconnected-(JP4-Pad11)") (class "Default")
      (node (ref "JP4") (pin "11") (pinfunction "11_11") (pintype "passive"))
    )
    (net (code "148") (name "unconnected-(JP4-Pad12)") (class "Default")
      (node (ref "JP4") (pin "12") (pinfunction "12_12") (pintype "passive"))
    )
    (net (code "149") (name "unconnected-(JP5-Pad1)") (class "Default")
      (node (ref "JP5") (pin "1") (pinfunction "1_1") (pintype "passive"))
    )
    (net (code "150") (name "unconnected-(JP5-Pad2)") (class "Default")
      (node (ref "JP5") (pin "2") (pinfunction "2_2") (pintype "passive"))
    )
    (net (code "151") (name "unconnected-(JP5-Pad3)") (class "Default")
      (node (ref "JP5") (pin "3") (pinfunction "3_3") (pintype "passive"))
    )
    (net (code "152") (name "unconnected-(JP5-Pad4)") (class "Default")
      (node (ref "JP5") (pin "4") (pinfunction "4_4") (pintype "passive"))
    )
    (net (code "153") (name "unconnected-(JP5-Pad5)") (class "Default")
      (node (ref "JP5") (pin "5") (pinfunction "5_5") (pintype "passive"))
    )
    (net (code "154") (name "unconnected-(JP5-Pad6)") (class "Default")
      (node (ref "JP5") (pin "6") (pinfunction "6_6") (pintype "passive"))
    )
    (net (code "155") (name "unconnected-(JP5-Pad7)") (class "Default")
      (node (ref "JP5") (pin "7") (pinfunction "7_7") (pintype "passive"))
    )
    (net (code "156") (name "unconnected-(JP5-Pad8)") (class "Default")
      (node (ref "JP5") (pin "8") (pinfunction "8_8") (pintype "passive"))
    )
    (net (code "157") (name "unconnected-(JP5-Pad9)") (class "Default")
      (node (ref "JP5") (pin "9") (pinfunction "9_9") (pintype "passive"))
    )
    (net (code "158") (name "unconnected-(JP5-Pad10)") (class "Default")
      (node (ref "JP5") (pin "10") (pinfunction "10_10") (pintype "passive"))
    )
    (net (code "159") (name "unconnected-(JP5-Pad11)") (class "Default")
      (node (ref "JP5") (pin "11") (pinfunction "11_11") (pintype "passive"))
    )
    (net (code "160") (name "unconnected-(JP5-Pad12)") (class "Default")
      (node (ref "JP5") (pin "12") (pinfunction "12_12") (pintype "passive"))
    )
    (net (code "161") (name "unconnected-(JP6-Pad1)") (class "Default")
      (node (ref "JP6") (pin "1") (pinfunction "1_1") (pintype "passive"))
    )
    (net (code "162") (name "unconnected-(JP6-Pad2)") (class "Default")
      (node (ref "JP6") (pin "2") (pinfunction "2_2") (pintype "passive"))
    )
    (net (code "163") (name "unconnected-(JP6-Pad3)") (class "Default")
      (node (ref "JP6") (pin "3") (pinfunction "3_3") (pintype "passive"))
    )
    (net (code "164") (name "unconnected-(JP6-Pad4)") (class "Default")
      (node (ref "JP6") (pin "4") (pinfunction "4_4") (pintype "passive"))
    )
    (net (code "165") (name "unconnected-(JP6-Pad5)") (class "Default")
      (node (ref "JP6") (pin "5") (pinfunction "5_5") (pintype "passive"))
    )
    (net (code "166") (name "unconnected-(JP6-Pad6)") (class "Default")
      (node (ref "JP6") (pin "6") (pinfunction "6_6") (pintype "passive"))
    )
    (net (code "167") (name "unconnected-(JP6-Pad7)") (class "Default")
      (node (ref "JP6") (pin "7") (pinfunction "7_7") (pintype "passive"))
    )
    (net (code "168") (name "unconnected-(JP6-Pad8)") (class "Default")
      (node (ref "JP6") (pin "8") (pinfunction "8_8") (pintype "passive"))
    )
    (net (code "169") (name "unconnected-(JP6-Pad9)") (class "Default")
      (node (ref "JP6") (pin "9") (pinfunction "9_9") (pintype "passive"))
    )
    (net (code "170") (name "unconnected-(JP6-Pad10)") (class "Default")
      (node (ref "JP6") (pin "10") (pinfunction "10_10") (pintype "passive"))
    )
    (net (code "171") (name "unconnected-(JP6-Pad11)") (class "Default")
      (node (ref "JP6") (pin "11") (pinfunction "11_11") (pintype "passive"))
    )
    (net (code "172") (name "unconnected-(JP6-Pad12)") (class "Default")
      (node (ref "JP6") (pin "12") (pinfunction "12_12") (pintype "passive"))
    )
    (net (code "173") (name "unconnected-(LEVELSHIFTIN-Pad2)") (class "Default")
      (node (ref "LEVELSHIFTIN") (pin "2") (pinfunction "2_2") (pintype "passive"))
    )
    (net (code "174") (name "unconnected-(LEVELSHIFTIN-Pad5)") (class "Default")
      (node (ref "LEVELSHIFTIN") (pin "5") (pinfunction "5_5") (pintype "passive"))
    )
    (net (code "175") (name "unconnected-(LEVELSHIFTOUT-Pad2)") (class "Default")
      (node (ref "LEVELSHIFTOUT") (pin "2") (pinfunction "2_2") (pintype "passive"))
    )
    (net (code "176") (name "unconnected-(LEVELSHIFTOUT-Pad5)") (class "Default")
      (node (ref "LEVELSHIFTOUT") (pin "5") (pinfunction "5_5") (pintype "passive"))
    )
    (net (code "177") (name "unconnected-(RCV_PWR-Pad2)") (class "Default")
      (node (ref "RCV_PWR") (pin "2") (pinfunction "2_2") (pintype "passive"))
    )
    (net (code "178") (name "unconnected-(RCV_PWR-Pad3)") (class "Default")
      (node (ref "RCV_PWR") (pin "3") (pinfunction "3_3") (pintype "passive"))
    )
    (net (code "179") (name "unconnected-(RCV_PWR-Pad4)") (class "Default")
      (node (ref "RCV_PWR") (pin "4") (pinfunction "4_4") (pintype "passive"))
    )
    (net (code "180") (name "unconnected-(RCV_PWR-Pad5)") (class "Default")
      (node (ref "RCV_PWR") (pin "5") (pinfunction "5_5") (pintype "passive"))
    )
    (net (code "181") (name "unconnected-(RCV_PWR-Pad6)") (class "Default")
      (node (ref "RCV_PWR") (pin "6") (pinfunction "6_6") (pintype "passive"))
    )
    (net (code "182") (name "unconnected-(RCV_PWR-Pad7)") (class "Default")
      (node (ref "RCV_PWR") (pin "7") (pinfunction "7_7") (pintype "passive"))
    )
    (net (code "183") (name "unconnected-(RCV_PWR-Pad8)") (class "Default")
      (node (ref "RCV_PWR") (pin "8") (pinfunction "8_8") (pintype "passive"))
    )
  )
)
